# Driver1.net
KiCad netlist of a schematic drawn in Altium Designer
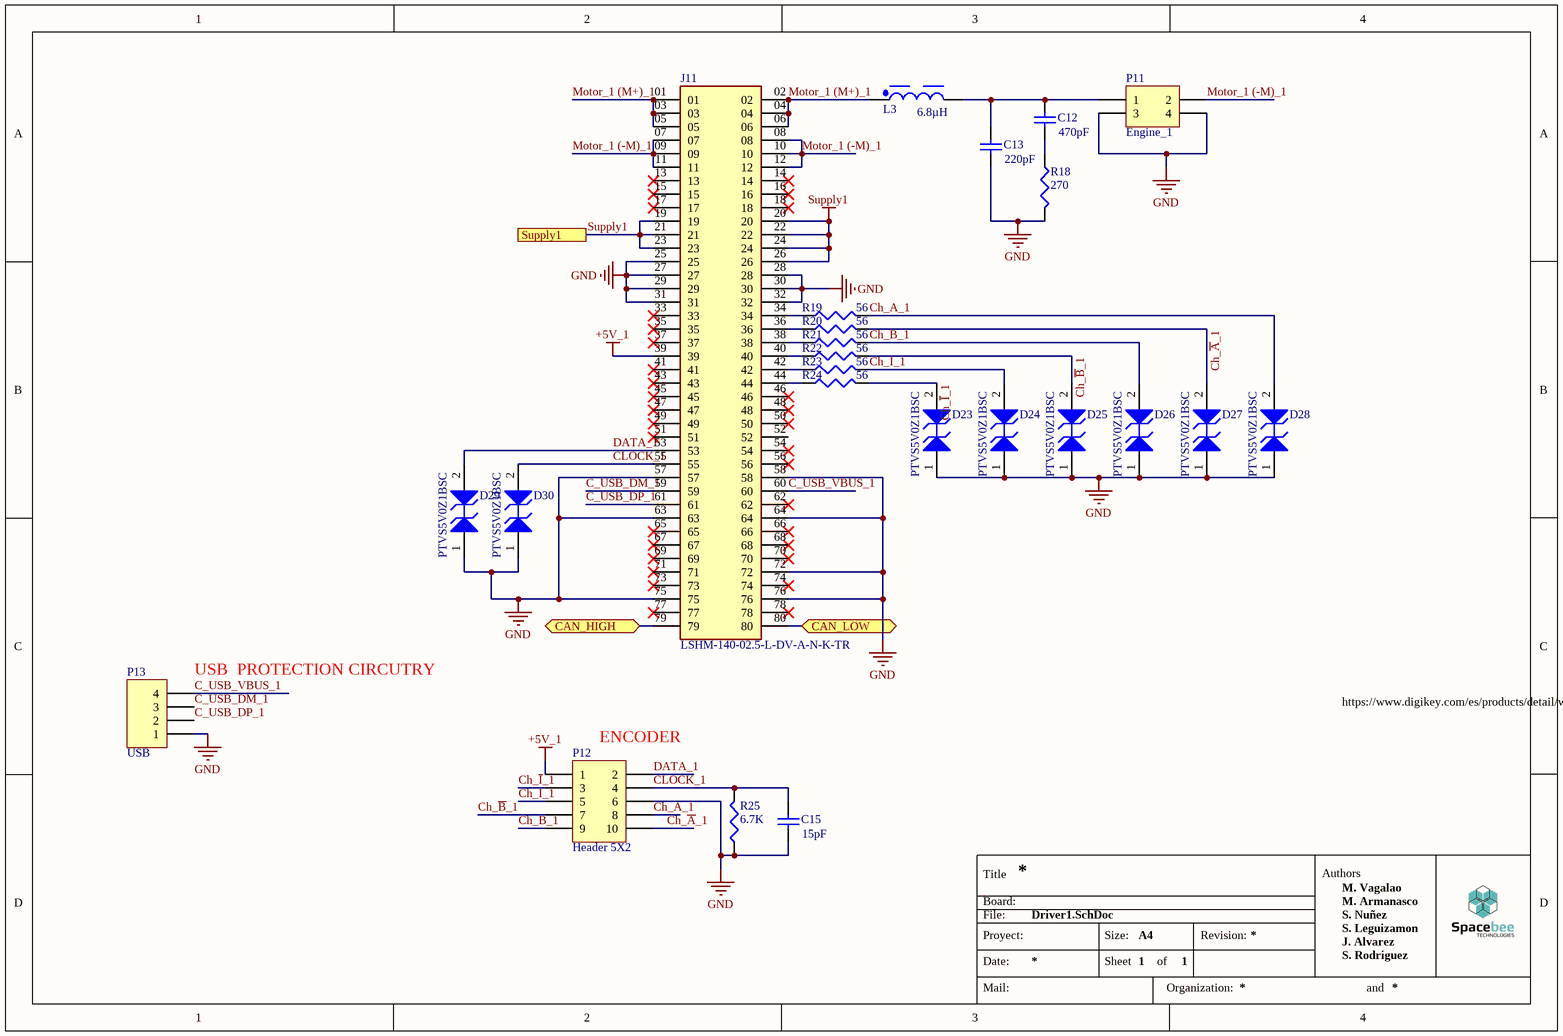
[diagram p0: Driver1.SchDoc]

(export (version "E")
  (design (tool "Eeschema 10.0.6"))
  (components
    (comp (ref "C12")
      (value "470pF")
      (footprint "1608[0603]")
      (description "Capacitor (Semiconductor SIM Model)")
      (fields (field (name "Comment") "Cap Semi") (field (name "PUBLISHER") "Altium Limited"))
      (libsource (lib "Miscellaneous Devices") (part "Cap Semi"))
    )
    (comp (ref "C13")
      (value "220pF")
      (footprint "1608[0603]")
      (description "Capacitor (Semiconductor SIM Model)")
      (fields (field (name "Comment") "Cap Semi") (field (name "PUBLISHER") "Altium Limited"))
      (libsource (lib "Miscellaneous Devices") (part "Cap Semi"))
    )
    (comp (ref "C15")
      (value "15pF")
      (footprint "1608[0603]")
      (description "Capacitor (Semiconductor SIM Model)")
      (fields (field (name "Comment") "Cap Semi") (field (name "PUBLISHER") "Altium Limited"))
      (libsource (lib "Miscellaneous Devices") (part "Cap Semi"))
    )
    (comp (ref "D23")
      (value "PTVS5V0Z1BSC")
      (footprint "SOD993B")
      (fields (field (name "MANUFACTURER") "On Semiconductor") (field (name "PARTNUMBER") "1SMB16CAT3"))
      (libsource (lib "DriverLib") (part "PTVS5V0Z1BSC"))
    )
    (comp (ref "D24")
      (value "PTVS5V0Z1BSC")
      (footprint "SOD993B")
      (fields (field (name "MANUFACTURER") "On Semiconductor") (field (name "PARTNUMBER") "1SMB16CAT3"))
      (libsource (lib "DriverLib") (part "PTVS5V0Z1BSC"))
    )
    (comp (ref "D25")
      (value "PTVS5V0Z1BSC")
      (footprint "SOD993B")
      (fields (field (name "MANUFACTURER") "On Semiconductor") (field (name "PARTNUMBER") "1SMB16CAT3"))
      (libsource (lib "DriverLib") (part "PTVS5V0Z1BSC"))
    )
    (comp (ref "D26")
      (value "PTVS5V0Z1BSC")
      (footprint "SOD993B")
      (fields (field (name "MANUFACTURER") "On Semiconductor") (field (name "PARTNUMBER") "1SMB16CAT3"))
      (libsource (lib "DriverLib") (part "PTVS5V0Z1BSC"))
    )
    (comp (ref "D27")
      (value "PTVS5V0Z1BSC")
      (footprint "SOD993B")
      (fields (field (name "MANUFACTURER") "On Semiconductor") (field (name "PARTNUMBER") "1SMB16CAT3"))
      (libsource (lib "DriverLib") (part "PTVS5V0Z1BSC"))
    )
    (comp (ref "D28")
      (value "PTVS5V0Z1BSC")
      (footprint "SOD993B")
      (fields (field (name "MANUFACTURER") "On Semiconductor") (field (name "PARTNUMBER") "1SMB16CAT3"))
      (libsource (lib "DriverLib") (part "PTVS5V0Z1BSC"))
    )
    (comp (ref "D29")
      (value "PTVS5V0Z1BSC")
      (footprint "SOD993B")
      (fields (field (name "MANUFACTURER") "On Semiconductor") (field (name "PARTNUMBER") "1SMB16CAT3"))
      (libsource (lib "DriverLib") (part "PTVS5V0Z1BSC"))
    )
    (comp (ref "D30")
      (value "PTVS5V0Z1BSC")
      (footprint "SOD993B")
      (fields (field (name "MANUFACTURER") "On Semiconductor") (field (name "PARTNUMBER") "1SMB16CAT3"))
      (libsource (lib "DriverLib") (part "PTVS5V0Z1BSC"))
    )
    (comp (ref "J11")
      (value "LSHM-140-02.5-L-DV-A-N-K-TR")
      (footprint "SAMTEC_LSHM-140-02.5-L-DV-A-N-K-TR")
      (description "LSHM - Samtec 0.50mm Razor Beam High-Speed Hermaphroditic Terminal / Socket Strip.")
      (libsource (lib "SpaceBee") (part "LSHM-140-02.5-L-DV-A-N-K-TR"))
    )
    (comp (ref "L3")
      (value "6.8µH")
      (footprint "WE-XHMA_6060")
      (description "WE-XHMA SMD Power Inductor, size 1090, 6.8µH, 10.5A, 7.16mΩ")
      (fields
        (field (name "MANUFACTURER PART NUMBER") "78439369068")
        (field (name "MANUFACTURER") "Wurth Elektronik")
      )
      (libsource (lib "DriverLib") (part "78439369068"))
    )
    (comp (ref "P11")
      (value "Engine_1")
      (footprint "MOLEX_1724480004")
      (description "Header, 2-Pin, Dual row")
      (fields (field (name "PUBLISHER") "Altium Limited"))
      (libsource (lib "SpaceBee") (part "Header 2X2"))
    )
    (comp (ref "P12")
      (value "Header 5X2")
      (footprint "CONN_HIF3FC-14PA-2.54DS(71)_HIR")
      (description "Header, 5-Pin, Dual row")
      (fields (field (name "PUBLISHER") "Altium Limited"))
      (libsource (lib "DriverLib") (part "Header 5X2"))
    )
    (comp (ref "P13")
      (value "USB")
      (footprint "HDR1X4")
      (description "Header, 4-Pin")
      (fields (field (name "PUBLISHER") "Altium Limited"))
      (libsource (lib "Miscellaneous Connectors") (part "Header 4"))
    )
    (comp (ref "R18")
      (value "270")
      (footprint "J1-0603")
      (description "Resistor")
      (fields (field (name "Comment") "Res3") (field (name "PUBLISHER") "Altium Limited"))
      (libsource (lib "Miscellaneous Devices") (part "Res3"))
    )
    (comp (ref "R19")
      (value "56")
      (footprint "J1-0603")
      (description "Resistor")
      (fields (field (name "Comment") "Res3") (field (name "PUBLISHER") "Altium Limited"))
      (libsource (lib "Miscellaneous Devices") (part "Res3"))
    )
    (comp (ref "R20")
      (value "56")
      (footprint "J1-0603")
      (description "Resistor")
      (fields (field (name "Comment") "Res3") (field (name "PUBLISHER") "Altium Limited"))
      (libsource (lib "Miscellaneous Devices") (part "Res3"))
    )
    (comp (ref "R21")
      (value "56")
      (footprint "J1-0603")
      (description "Resistor")
      (fields (field (name "Comment") "Res3") (field (name "PUBLISHER") "Altium Limited"))
      (libsource (lib "Miscellaneous Devices") (part "Res3"))
    )
    (comp (ref "R22")
      (value "56")
      (footprint "J1-0603")
      (description "Resistor")
      (fields (field (name "Comment") "Res3") (field (name "PUBLISHER") "Altium Limited"))
      (libsource (lib "Miscellaneous Devices") (part "Res3"))
    )
    (comp (ref "R23")
      (value "56")
      (footprint "J1-0603")
      (description "Resistor")
      (fields (field (name "Comment") "Res3") (field (name "PUBLISHER") "Altium Limited"))
      (libsource (lib "Miscellaneous Devices") (part "Res3"))
    )
    (comp (ref "R24")
      (value "56")
      (footprint "J1-0603")
      (description "Resistor")
      (fields (field (name "Comment") "Res3") (field (name "PUBLISHER") "Altium Limited"))
      (libsource (lib "Miscellaneous Devices") (part "Res3"))
    )
    (comp (ref "R25")
      (value "6.7K")
      (footprint "J1-0603")
      (description "Resistor")
      (fields (field (name "Comment") "Res3") (field (name "PUBLISHER") "Altium Limited"))
      (libsource (lib "Miscellaneous Devices") (part "Res3"))
    )
  )
  (nets
    (net (code "1") (name "+5V_1") (class "Default")
      (node (ref "J11") (pin "39") (pinfunction "39_39") (pintype "passive"))
      (node (ref "P12") (pin "1") (pinfunction "1_1") (pintype "passive"))
    )
    (net (code "2") (name "/CAN_HIGH") (class "Default")
      (node (ref "J11") (pin "79") (pinfunction "79_79") (pintype "passive"))
    )
    (net (code "3") (name "/CAN_LOW") (class "Default")
      (node (ref "J11") (pin "80") (pinfunction "80_80") (pintype "passive"))
    )
    (net (code "4") (name "/CLOCK_1") (class "Default")
      (node (ref "C15") (pin "1") (pinfunction "1_1") (pintype "passive"))
      (node (ref "D30") (pin "2") (pinfunction "A2_2") (pintype "passive"))
      (node (ref "J11") (pin "55") (pinfunction "55_55") (pintype "passive"))
      (node (ref "P12") (pin "4") (pinfunction "4_4") (pintype "passive"))
      (node (ref "R25") (pin "2") (pinfunction "2_2") (pintype "passive"))
    )
    (net (code "5") (name "/C_USB_DM_1") (class "Default")
      (node (ref "J11") (pin "59") (pinfunction "59_59") (pintype "passive"))
      (node (ref "P13") (pin "3") (pinfunction "3_3") (pintype "passive"))
    )
    (net (code "6") (name "/C_USB_DP_1") (class "Default")
      (node (ref "J11") (pin "61") (pinfunction "61_61") (pintype "passive"))
      (node (ref "P13") (pin "2") (pinfunction "2_2") (pintype "passive"))
    )
    (net (code "7") (name "/C_USB_VBUS_1") (class "Default")
      (node (ref "J11") (pin "60") (pinfunction "60_60") (pintype "passive"))
      (node (ref "P13") (pin "4") (pinfunction "4_4") (pintype "passive"))
    )
    (net (code "8") (name "/Ch_A_1") (class "Default")
      (node (ref "D28") (pin "2") (pinfunction "A2_2") (pintype "passive"))
      (node (ref "P12") (pin "8") (pinfunction "8_8") (pintype "passive"))
      (node (ref "R19") (pin "2") (pinfunction "2_2") (pintype "passive"))
    )
    (net (code "9") (name "/Ch_B_1") (class "Default")
      (node (ref "D26") (pin "2") (pinfunction "A2_2") (pintype "passive"))
      (node (ref "P12") (pin "9") (pinfunction "9_9") (pintype "passive"))
      (node (ref "R21") (pin "2") (pinfunction "2_2") (pintype "passive"))
    )
    (net (code "10") (name "/Ch_I_1") (class "Default")
      (node (ref "D24") (pin "2") (pinfunction "A2_2") (pintype "passive"))
      (node (ref "P12") (pin "5") (pinfunction "5_5") (pintype "passive"))
      (node (ref "R23") (pin "2") (pinfunction "2_2") (pintype "passive"))
    )
    (net (code "11") (name "/Ch_~{A}_1") (class "Default")
      (node (ref "D27") (pin "2") (pinfunction "A2_2") (pintype "passive"))
      (node (ref "P12") (pin "10") (pinfunction "10_10") (pintype "passive"))
      (node (ref "R20") (pin "2") (pinfunction "2_2") (pintype "passive"))
    )
    (net (code "12") (name "/Ch_~{B}_1") (class "Default")
      (node (ref "D25") (pin "2") (pinfunction "A2_2") (pintype "passive"))
      (node (ref "P12") (pin "7") (pinfunction "7_7") (pintype "passive"))
      (node (ref "R22") (pin "2") (pinfunction "2_2") (pintype "passive"))
    )
    (net (code "13") (name "/Ch_~{I}_1") (class "Default")
      (node (ref "D23") (pin "2") (pinfunction "A2_2") (pintype "passive"))
      (node (ref "P12") (pin "3") (pinfunction "3_3") (pintype "passive"))
      (node (ref "R24") (pin "2") (pinfunction "2_2") (pintype "passive"))
    )
    (net (code "14") (name "/DATA_1") (class "Default")
      (node (ref "D29") (pin "2") (pinfunction "A2_2") (pintype "passive"))
      (node (ref "J11") (pin "53") (pinfunction "53_53") (pintype "passive"))
      (node (ref "P12") (pin "2") (pinfunction "2_2") (pintype "passive"))
    )
    (net (code "15") (name "/Motor_1 (-M)_1") (class "Default")
      (node (ref "J11") (pin "07") (pinfunction "07_07") (pintype "passive"))
      (node (ref "J11") (pin "08") (pinfunction "08_08") (pintype "passive"))
      (node (ref "J11") (pin "09") (pinfunction "09_09") (pintype "passive"))
      (node (ref "J11") (pin "10") (pinfunction "10_10") (pintype "passive"))
      (node (ref "J11") (pin "11") (pinfunction "11_11") (pintype "passive"))
      (node (ref "J11") (pin "12") (pinfunction "12_12") (pintype "passive"))
      (node (ref "P11") (pin "2") (pinfunction "2_2") (pintype "passive"))
    )
    (net (code "16") (name "/Motor_1 (M+)_1") (class "Default")
      (node (ref "J11") (pin "01") (pinfunction "01_01") (pintype "passive"))
      (node (ref "J11") (pin "02") (pinfunction "02_02") (pintype "passive"))
      (node (ref "J11") (pin "03") (pinfunction "03_03") (pintype "passive"))
      (node (ref "J11") (pin "04") (pinfunction "04_04") (pintype "passive"))
      (node (ref "J11") (pin "05") (pinfunction "05_05") (pintype "passive"))
      (node (ref "J11") (pin "06") (pinfunction "06_06") (pintype "passive"))
      (node (ref "L3") (pin "1") (pinfunction "1_1") (pintype "passive"))
    )
    (net (code "17") (name "GND") (class "Default")
      (node (ref "C13") (pin "2") (pinfunction "2_2") (pintype "passive"))
      (node (ref "C15") (pin "2") (pinfunction "2_2") (pintype "passive"))
      (node (ref "D23") (pin "1") (pinfunction "A1_1") (pintype "passive"))
      (node (ref "D24") (pin "1") (pinfunction "A1_1") (pintype "passive"))
      (node (ref "D25") (pin "1") (pinfunction "A1_1") (pintype "passive"))
      (node (ref "D26") (pin "1") (pinfunction "A1_1") (pintype "passive"))
      (node (ref "D27") (pin "1") (pinfunction "A1_1") (pintype "passive"))
      (node (ref "D28") (pin "1") (pinfunction "A1_1") (pintype "passive"))
      (node (ref "D29") (pin "1") (pinfunction "A1_1") (pintype "passive"))
      (node (ref "D30") (pin "1") (pinfunction "A1_1") (pintype "passive"))
      (node (ref "J11") (pin "25") (pinfunction "25_25") (pintype "passive"))
      (node (ref "J11") (pin "27") (pinfunction "27_27") (pintype "passive"))
      (node (ref "J11") (pin "28") (pinfunction "28_28") (pintype "passive"))
      (node (ref "J11") (pin "29") (pinfunction "29_29") (pintype "passive"))
      (node (ref "J11") (pin "30") (pinfunction "30_30") (pintype "passive"))
      (node (ref "J11") (pin "31") (pinfunction "31_31") (pintype "passive"))
      (node (ref "J11") (pin "32") (pinfunction "32_32") (pintype "passive"))
      (node (ref "J11") (pin "57") (pinfunction "57_57") (pintype "passive"))
      (node (ref "J11") (pin "58") (pinfunction "58_58") (pintype "passive"))
      (node (ref "J11") (pin "63") (pinfunction "63_63") (pintype "passive"))
      (node (ref "J11") (pin "64") (pinfunction "64_64") (pintype "passive"))
      (node (ref "J11") (pin "72") (pinfunction "72_72") (pintype "passive"))
      (node (ref "J11") (pin "75") (pinfunction "75_75") (pintype "passive"))
      (node (ref "J11") (pin "76") (pinfunction "76_76") (pintype "passive"))
      (node (ref "P11") (pin "3") (pinfunction "3_3") (pintype "passive"))
      (node (ref "P11") (pin "4") (pinfunction "4_4") (pintype "passive"))
      (node (ref "P12") (pin "6") (pinfunction "6_6") (pintype "passive"))
      (node (ref "P13") (pin "1") (pinfunction "1_1") (pintype "passive"))
      (node (ref "R18") (pin "2") (pinfunction "2_2") (pintype "passive"))
      (node (ref "R25") (pin "1") (pinfunction "1_1") (pintype "passive"))
    )
    (net (code "18") (name "Net-(C12-Pad1)") (class "Default")
      (node (ref "C12") (pin "1") (pinfunction "1_1") (pintype "passive"))
      (node (ref "C13") (pin "1") (pinfunction "1_1") (pintype "passive"))
      (node (ref "L3") (pin "2") (pinfunction "2_2") (pintype "passive"))
      (node (ref "P11") (pin "1") (pinfunction "1_1") (pintype "passive"))
    )
    (net (code "19") (name "Net-(C12-Pad2)") (class "Default")
      (node (ref "C12") (pin "2") (pinfunction "2_2") (pintype "passive"))
      (node (ref "R18") (pin "1") (pinfunction "1_1") (pintype "passive"))
    )
    (net (code "20") (name "Net-(J11-Pad34)") (class "Default")
      (node (ref "J11") (pin "34") (pinfunction "34_34") (pintype "passive"))
      (node (ref "R19") (pin "1") (pinfunction "1_1") (pintype "passive"))
    )
    (net (code "21") (name "Net-(J11-Pad36)") (class "Default")
      (node (ref "J11") (pin "36") (pinfunction "36_36") (pintype "passive"))
      (node (ref "R20") (pin "1") (pinfunction "1_1") (pintype "passive"))
    )
    (net (code "22") (name "Net-(J11-Pad38)") (class "Default")
      (node (ref "J11") (pin "38") (pinfunction "38_38") (pintype "passive"))
      (node (ref "R21") (pin "1") (pinfunction "1_1") (pintype "passive"))
    )
    (net (code "23") (name "Net-(J11-Pad40)") (class "Default")
      (node (ref "J11") (pin "40") (pinfunction "40_40") (pintype "passive"))
      (node (ref "R22") (pin "1") (pinfunction "1_1") (pintype "passive"))
    )
    (net (code "24") (name "Net-(J11-Pad42)") (class "Default")
      (node (ref "J11") (pin "42") (pinfunction "42_42") (pintype "passive"))
      (node (ref "R23") (pin "1") (pinfunction "1_1") (pintype "passive"))
    )
    (net (code "25") (name "Net-(J11-Pad44)") (class "Default")
      (node (ref "J11") (pin "44") (pinfunction "44_44") (pintype "passive"))
      (node (ref "R24") (pin "1") (pinfunction "1_1") (pintype "passive"))
    )
    (net (code "26") (name "Supply1") (class "Default")
      (node (ref "J11") (pin "19") (pinfunction "19_19") (pintype "passive"))
      (node (ref "J11") (pin "20") (pinfunction "20_20") (pintype "passive"))
      (node (ref "J11") (pin "21") (pinfunction "21_21") (pintype "passive"))
      (node (ref "J11") (pin "22") (pinfunction "22_22") (pintype "passive"))
      (node (ref "J11") (pin "23") (pinfunction "23_23") (pintype "passive"))
      (node (ref "J11") (pin "24") (pinfunction "24_24") (pintype "passive"))
      (node (ref "J11") (pin "26") (pinfunction "26_26") (pintype "passive"))
    )
    (net (code "27") (name "unconnected-(J11-Pad13)") (class "Default")
      (node (ref "J11") (pin "13") (pinfunction "13_13") (pintype "passive+no_connect"))
    )
    (net (code "28") (name "unconnected-(J11-Pad14)") (class "Default")
      (node (ref "J11") (pin "14") (pinfunction "14_14") (pintype "passive+no_connect"))
    )
    (net (code "29") (name "unconnected-(J11-Pad15)") (class "Default")
      (node (ref "J11") (pin "15") (pinfunction "15_15") (pintype "passive+no_connect"))
    )
    (net (code "30") (name "unconnected-(J11-Pad16)") (class "Default")
      (node (ref "J11") (pin "16") (pinfunction "16_16") (pintype "passive+no_connect"))
    )
    (net (code "31") (name "unconnected-(J11-Pad17)") (class "Default")
      (node (ref "J11") (pin "17") (pinfunction "17_17") (pintype "passive+no_connect"))
    )
    (net (code "32") (name "unconnected-(J11-Pad18)") (class "Default")
      (node (ref "J11") (pin "18") (pinfunction "18_18") (pintype "passive+no_connect"))
    )
    (net (code "33") (name "unconnected-(J11-Pad33)") (class "Default")
      (node (ref "J11") (pin "33") (pinfunction "33_33") (pintype "passive+no_connect"))
    )
    (net (code "34") (name "unconnected-(J11-Pad35)") (class "Default")
      (node (ref "J11") (pin "35") (pinfunction "35_35") (pintype "passive+no_connect"))
    )
    (net (code "35") (name "unconnected-(J11-Pad37)") (class "Default")
      (node (ref "J11") (pin "37") (pinfunction "37_37") (pintype "passive+no_connect"))
    )
    (net (code "36") (name "unconnected-(J11-Pad41)") (class "Default")
      (node (ref "J11") (pin "41") (pinfunction "41_41") (pintype "passive+no_connect"))
    )
    (net (code "37") (name "unconnected-(J11-Pad43)") (class "Default")
      (node (ref "J11") (pin "43") (pinfunction "43_43") (pintype "passive+no_connect"))
    )
    (net (code "38") (name "unconnected-(J11-Pad45)") (class "Default")
      (node (ref "J11") (pin "45") (pinfunction "45_45") (pintype "passive+no_connect"))
    )
    (net (code "39") (name "unconnected-(J11-Pad46)") (class "Default")
      (node (ref "J11") (pin "46") (pinfunction "46_46") (pintype "passive+no_connect"))
    )
    (net (code "40") (name "unconnected-(J11-Pad47)") (class "Default")
      (node (ref "J11") (pin "47") (pinfunction "47_47") (pintype "passive+no_connect"))
    )
    (net (code "41") (name "unconnected-(J11-Pad48)") (class "Default")
      (node (ref "J11") (pin "48") (pinfunction "48_48") (pintype "passive+no_connect"))
    )
    (net (code "42") (name "unconnected-(J11-Pad49)") (class "Default")
      (node (ref "J11") (pin "49") (pinfunction "49_49") (pintype "passive+no_connect"))
    )
    (net (code "43") (name "unconnected-(J11-Pad50)") (class "Default")
      (node (ref "J11") (pin "50") (pinfunction "50_50") (pintype "passive+no_connect"))
    )
    (net (code "44") (name "unconnected-(J11-Pad51)") (class "Default")
      (node (ref "J11") (pin "51") (pinfunction "51_51") (pintype "passive+no_connect"))
    )
    (net (code "45") (name "unconnected-(J11-Pad52)") (class "Default")
      (node (ref "J11") (pin "52") (pinfunction "52_52") (pintype "passive"))
    )
    (net (code "46") (name "unconnected-(J11-Pad54)") (class "Default")
      (node (ref "J11") (pin "54") (pinfunction "54_54") (pintype "passive+no_connect"))
    )
    (net (code "47") (name "unconnected-(J11-Pad56)") (class "Default")
      (node (ref "J11") (pin "56") (pinfunction "56_56") (pintype "passive+no_connect"))
    )
    (net (code "48") (name "unconnected-(J11-Pad62)") (class "Default")
      (node (ref "J11") (pin "62") (pinfunction "62_62") (pintype "passive+no_connect"))
    )
    (net (code "49") (name "unconnected-(J11-Pad65)") (class "Default")
      (node (ref "J11") (pin "65") (pinfunction "65_65") (pintype "passive+no_connect"))
    )
    (net (code "50") (name "unconnected-(J11-Pad66)") (class "Default")
      (node (ref "J11") (pin "66") (pinfunction "66_66") (pintype "passive+no_connect"))
    )
    (net (code "51") (name "unconnected-(J11-Pad67)") (class "Default")
      (node (ref "J11") (pin "67") (pinfunction "67_67") (pintype "passive+no_connect"))
    )
    (net (code "52") (name "unconnected-(J11-Pad68)") (class "Default")
      (node (ref "J11") (pin "68") (pinfunction "68_68") (pintype "passive+no_connect"))
    )
    (net (code "53") (name "unconnected-(J11-Pad69)") (class "Default")
      (node (ref "J11") (pin "69") (pinfunction "69_69") (pintype "passive+no_connect"))
    )
    (net (code "54") (name "unconnected-(J11-Pad70)") (class "Default")
      (node (ref "J11") (pin "70") (pinfunction "70_70") (pintype "passive+no_connect"))
    )
    (net (code "55") (name "unconnected-(J11-Pad71)") (class "Default")
      (node (ref "J11") (pin "71") (pinfunction "71_71") (pintype "passive+no_connect"))
    )
    (net (code "56") (name "unconnected-(J11-Pad73)") (class "Default")
      (node (ref "J11") (pin "73") (pinfunction "73_73") (pintype "passive+no_connect"))
    )
    (net (code "57") (name "unconnected-(J11-Pad74)") (class "Default")
      (node (ref "J11") (pin "74") (pinfunction "74_74") (pintype "passive+no_connect"))
    )
    (net (code "58") (name "unconnected-(J11-Pad77)") (class "Default")
      (node (ref "J11") (pin "77") (pinfunction "77_77") (pintype "passive+no_connect"))
    )
    (net (code "59") (name "unconnected-(J11-Pad78)") (class "Default")
      (node (ref "J11") (pin "78") (pinfunction "78_78") (pintype "passive+no_connect"))
    )
  )
)
